# Aux_Supply.net
KiCad netlist of a schematic drawn in Altium Designer
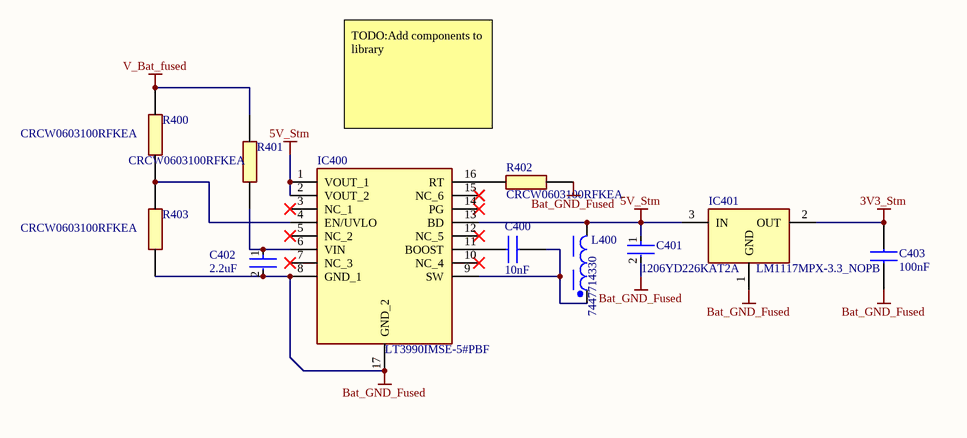
[diagram p0: Aux_Supply.SchDoc]

(export (version "E")
  (design (tool "Eeschema 10.0.6"))
  (components
    (comp (ref "C400")
      (value "10nF")
      (footprint "SamacSys:CAPC1608X90N")
      (description "Capacitor")
      (fields
        (field (name "MANUFACTURER_PART_NUMBER") "06031C103K4Z2A")
        (field (name "MOUSER PART NUMBER") "581-06031C103K4Z2A")
      )
      (libsource (lib "SamacSys") (part "06031C103K4Z2A"))
    )
    (comp (ref "C401")
      (value "1206YD226KAT2A")
      (footprint "FP-1206-L_3_2_0_2-W_1_6_0-IPC_C")
      (description "General Purpose Ceramic Capacitor, 1206, 22uF, 10%, X5R, 15%, 16V")
      (fields (field (name "TOLERANCE") "10%"))
      (libsource (lib "Altium Content Vault") (part "02cd4be3c70576c341d710602a673aa"))
    )
    (comp (ref "C402")
      (value "C3216X7S2A225K160AB")
      (footprint "FP-C3216-160-0_2-IPC_B")
      (description "Multilayer Ceramic Capacitors 2.2uF ±10% 100V X7S SMD 1206")
      (fields
        (field (name "TOLERANCE") "10%")
        (field (name "CAPACITANCE") "2.2uF")
        (field (name "VOLTAGE") "100V")
      )
      (libsource (lib "Altium Content Vault") (part "11868f565c42a9108669ba33697ecf6"))
    )
    (comp (ref "C403")
      (value "100nF")
      (footprint "SamacSys:CAPC1608X90N")
      (description "Capacitor")
      (fields
        (field (name "MANUFACTURER_PART_NUMBER") "0603YG104ZAT2A")
        (field (name "MOUSER PART NUMBER") "581-0603YG104ZAT2A")
      )
      (libsource (lib "SamacSys") (part "0603YG104ZAT2A"))
    )
    (comp (ref "IC400")
      (value "LT3990IMSE-5#PBF")
      (footprint "SamacSys:SOP50P490X110-17N")
      (description "Integrated Circuit")
      (fields (field (name "MOUSER PART NUMBER") "584-LT3990IMSE-5#PBF"))
      (libsource (lib "SamacSys") (part "LT3990IMSE-5#PBF"))
    )
    (comp (ref "IC401")
      (value "LM1117MPX-3.3_NOPB")
      (footprint "SamacSys:SOT230P700X180-4N")
      (description "Integrated Circuit")
      (fields
        (field (name "MANUFACTURER_PART_NUMBER") "LM1117MPX-3.3/NOPB")
        (field (name "MOUSER PART NUMBER") "926-LM1117MPX3.3NOPB")
      )
      (libsource (lib "SamacSys") (part "LM1117MPX-3.3_NOPB"))
    )
    (comp (ref "L400")
      (value "7447714330")
      (footprint "WE-PD_1050P")
      (fields (field (name "TOLERANCE") "20%"))
      (libsource (lib "Altium Content Vault") (part "Inductor - 2"))
    )
    (comp (ref "R400")
      (value "CRCW0603100RFKEA")
      (footprint "SamacSys:RESC1608X50N")
      (description "Resistor")
      (fields (field (name "MOUSER PART NUMBER") "71-CRCW0603-100-E3"))
      (libsource (lib "SamacSys") (part "CRCW0603100RFKEA"))
    )
    (comp (ref "R401")
      (value "CRCW0603100RFKEA")
      (footprint "SamacSys:RESC1608X50N")
      (description "Resistor")
      (fields (field (name "MOUSER PART NUMBER") "71-CRCW0603-100-E3"))
      (libsource (lib "") (part "CRCW0603100RFKEA_1"))
    )
    (comp (ref "R402")
      (value "CRCW0603100RFKEA")
      (footprint "SamacSys:RESC1608X50N")
      (description "Resistor")
      (fields (field (name "MOUSER PART NUMBER") "71-CRCW0603-100-E3"))
      (libsource (lib "") (part "CRCW0603100RFKEA_2"))
    )
    (comp (ref "R403")
      (value "CRCW0603100RFKEA")
      (footprint "SamacSys:RESC1608X50N")
      (description "Resistor")
      (fields (field (name "MOUSER PART NUMBER") "71-CRCW0603-100-E3"))
      (libsource (lib "SamacSys") (part "CRCW0603100RFKEA"))
    )
  )
  (nets
    (net (code "1") (name "3V3_Stm") (class "Default")
      (node (ref "C403") (pin "2") (pinfunction "2_2") (pintype "passive"))
      (node (ref "IC401") (pin "2") (pinfunction "OUT_2") (pintype "passive"))
    )
    (net (code "2") (name "5V_Stm") (class "Default")
      (node (ref "C401") (pin "1") (pinfunction "1_1") (pintype "passive"))
      (node (ref "IC400") (pin "1") (pinfunction "VOUT_1_1") (pintype "passive"))
      (node (ref "IC400") (pin "13") (pinfunction "BD_13") (pintype "passive"))
      (node (ref "IC400") (pin "2") (pinfunction "VOUT_2_2") (pintype "passive"))
      (node (ref "IC401") (pin "3") (pinfunction "IN_3") (pintype "passive"))
      (node (ref "L400") (pin "2") (pinfunction "2_2") (pintype "passive"))
    )
    (net (code "3") (name "Bat_GND_Fused") (class "Default")
      (node (ref "C401") (pin "2") (pinfunction "2_2") (pintype "passive"))
      (node (ref "C402") (pin "2") (pinfunction "2_2") (pintype "passive"))
      (node (ref "C403") (pin "1") (pinfunction "1_1") (pintype "passive"))
      (node (ref "IC400") (pin "17") (pinfunction "GND_2_17") (pintype "passive"))
      (node (ref "IC400") (pin "8") (pinfunction "GND_1_8") (pintype "passive"))
      (node (ref "IC401") (pin "1") (pinfunction "GND_1") (pintype "passive"))
      (node (ref "R402") (pin "2") (pinfunction "2_2") (pintype "passive"))
      (node (ref "R403") (pin "1") (pinfunction "1_1") (pintype "passive"))
    )
    (net (code "4") (name "Net-(IC400-BOOST)") (class "Default")
      (node (ref "C400") (pin "2") (pinfunction "2_2") (pintype "passive"))
      (node (ref "IC400") (pin "11") (pinfunction "BOOST_11") (pintype "passive"))
    )
    (net (code "5") (name "Net-(IC400-EN{slash}UVLO)") (class "Default")
      (node (ref "IC400") (pin "4") (pinfunction "EN/UVLO_4") (pintype "passive"))
      (node (ref "R400") (pin "1") (pinfunction "1_1") (pintype "passive"))
      (node (ref "R403") (pin "2") (pinfunction "2_2") (pintype "passive"))
    )
    (net (code "6") (name "Net-(IC400-RT)") (class "Default")
      (node (ref "IC400") (pin "16") (pinfunction "RT_16") (pintype "passive"))
      (node (ref "R402") (pin "1") (pinfunction "1_1") (pintype "passive"))
    )
    (net (code "7") (name "Net-(IC400-SW)") (class "Default")
      (node (ref "C400") (pin "1") (pinfunction "1_1") (pintype "passive"))
      (node (ref "IC400") (pin "9") (pinfunction "SW_9") (pintype "passive"))
      (node (ref "L400") (pin "1") (pinfunction "1_1") (pintype "passive"))
    )
    (net (code "8") (name "Net-(IC400-VIN)") (class "Default")
      (node (ref "C402") (pin "1") (pinfunction "1_1") (pintype "passive"))
      (node (ref "IC400") (pin "6") (pinfunction "VIN_6") (pintype "passive"))
      (node (ref "R401") (pin "2") (pinfunction "2_2") (pintype "passive"))
    )
    (net (code "9") (name "V_Bat_fused") (class "Default")
      (node (ref "R400") (pin "2") (pinfunction "2_2") (pintype "passive"))
      (node (ref "R401") (pin "1") (pinfunction "1_1") (pintype "passive"))
    )
    (net (code "10") (name "unconnected-(IC400-NC_1-Pad3)") (class "Default")
      (node (ref "IC400") (pin "3") (pinfunction "NC_1_3") (pintype "passive+no_connect"))
    )
    (net (code "11") (name "unconnected-(IC400-NC_2-Pad5)") (class "Default")
      (node (ref "IC400") (pin "5") (pinfunction "NC_2_5") (pintype "passive+no_connect"))
    )
    (net (code "12") (name "unconnected-(IC400-NC_3-Pad7)") (class "Default")
      (node (ref "IC400") (pin "7") (pinfunction "NC_3_7") (pintype "passive+no_connect"))
    )
    (net (code "13") (name "unconnected-(IC400-NC_4-Pad10)") (class "Default")
      (node (ref "IC400") (pin "10") (pinfunction "NC_4_10") (pintype "passive+no_connect"))
    )
    (net (code "14") (name "unconnected-(IC400-NC_5-Pad12)") (class "Default")
      (node (ref "IC400") (pin "12") (pinfunction "NC_5_12") (pintype "passive+no_connect"))
    )
    (net (code "15") (name "unconnected-(IC400-NC_6-Pad15)") (class "Default")
      (node (ref "IC400") (pin "15") (pinfunction "NC_6_15") (pintype "passive+no_connect"))
    )
    (net (code "16") (name "unconnected-(IC400-PG-Pad14)") (class "Default")
      (node (ref "IC400") (pin "14") (pinfunction "PG_14") (pintype "passive+no_connect"))
    )
  )
)
